# BRAWN.net
KiCad netlist of a schematic drawn in Altium Designer
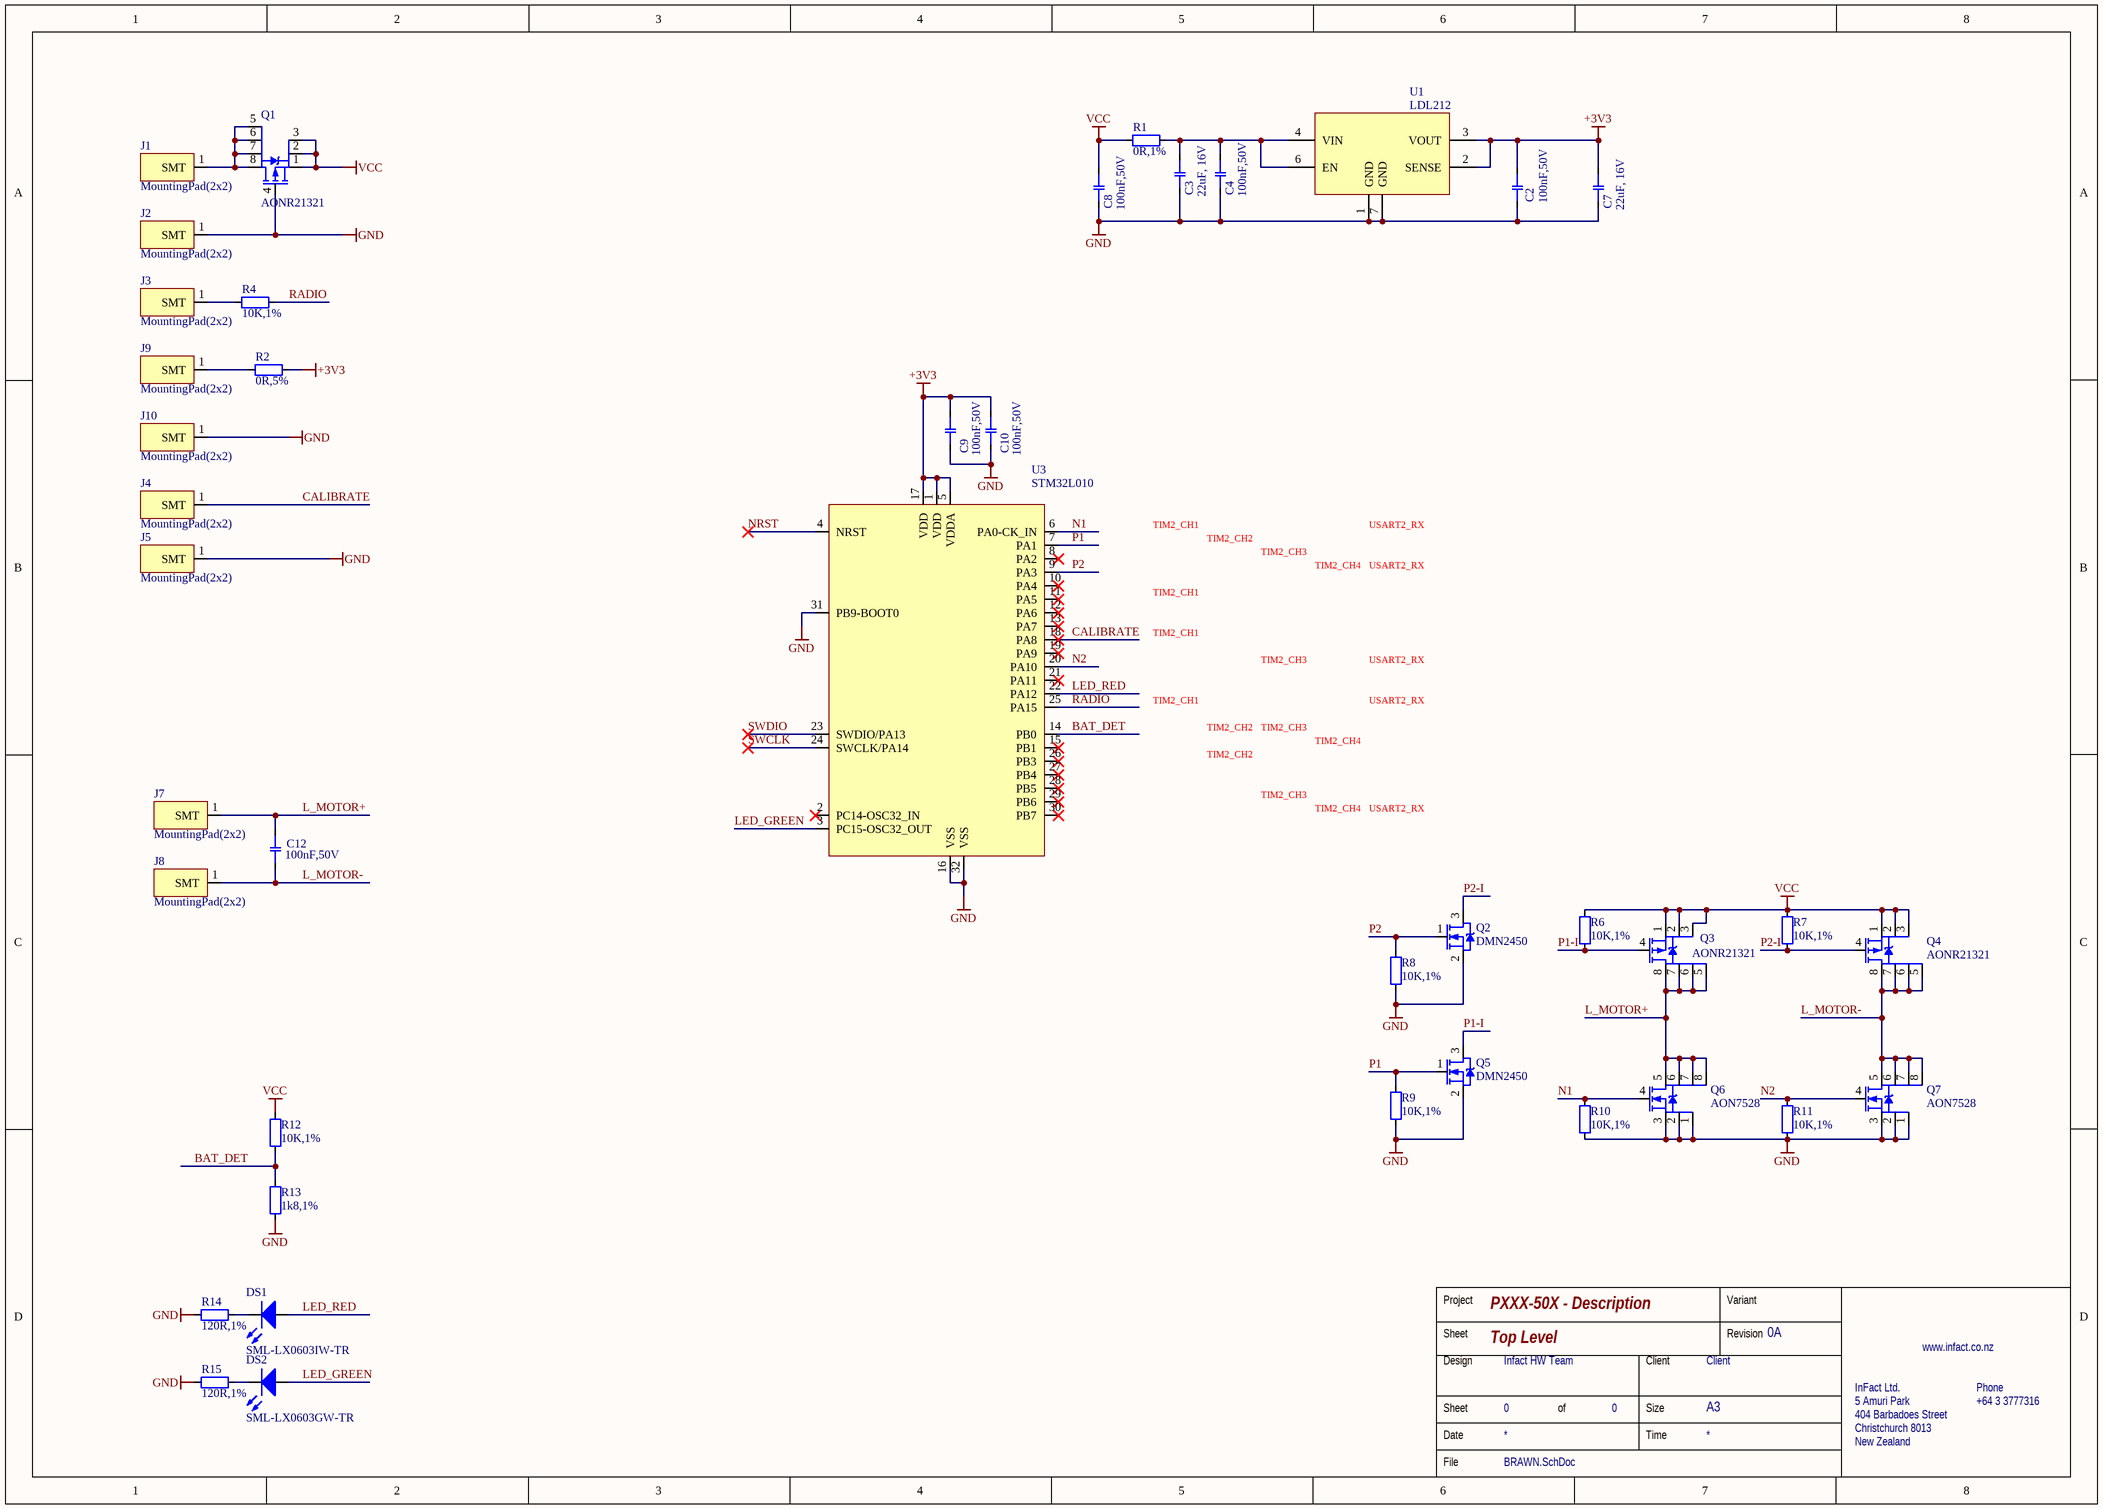
[diagram p0: BRAWN.SchDoc]

(export (version "E")
  (design (tool "Eeschema 10.0.6"))
  (components
    (comp (ref "C2")
      (value "100nF,50V")
      (footprint "CAPC1005X05N_0402")
      (description "CAP CER 100nF 50V X7R 0402")
      (fields (field (name "MANUFACTURER") "Taiyo Yuden") (field (name "TOLERANCE") "10%"))
      (libsource (lib "library") (part "CAP-NP_1"))
    )
    (comp (ref "C3")
      (value "22uF, 16V")
      (footprint "CAPC2012X12N_0805")
      (description "CAP CER 22UF 16V X5R 0805")
      (fields (field (name "MANUFACTURER") "Samsung Electro-Mechanics") (field (name "TOLERANCE") "10%"))
      (libsource (lib "library") (part "CAP-NP_1"))
    )
    (comp (ref "C4")
      (value "100nF,50V")
      (footprint "CAPC1005X05N_0402")
      (description "CAP CER 100nF 50V X7R 0402")
      (fields (field (name "MANUFACTURER") "Taiyo Yuden") (field (name "TOLERANCE") "10%"))
      (libsource (lib "library") (part "CAP-NP_1"))
    )
    (comp (ref "C7")
      (value "22uF, 16V")
      (footprint "CAPC2012X12N_0805")
      (description "CAP CER 22UF 16V X5R 0805")
      (fields (field (name "MANUFACTURER") "Samsung Electro-Mechanics") (field (name "TOLERANCE") "10%"))
      (libsource (lib "library") (part "CAP-NP_1"))
    )
    (comp (ref "C8")
      (value "100nF,50V")
      (footprint "CAPC1005X05N_0402")
      (description "CAP CER 100nF 50V X7R 0402")
      (fields (field (name "MANUFACTURER") "Taiyo Yuden") (field (name "TOLERANCE") "10%"))
      (libsource (lib "library") (part "CAP-NP_1"))
    )
    (comp (ref "C9")
      (value "100nF,50V")
      (footprint "CAPC1005X05N_0402")
      (description "CAP CER 100nF 50V X7R 0402")
      (fields (field (name "MANUFACTURER") "Taiyo Yuden") (field (name "TOLERANCE") "10%"))
      (libsource (lib "library") (part "CAP-NP_1"))
    )
    (comp (ref "C10")
      (value "100nF,50V")
      (footprint "CAPC1005X05N_0402")
      (description "CAP CER 100nF 50V X7R 0402")
      (fields (field (name "MANUFACTURER") "Taiyo Yuden") (field (name "TOLERANCE") "10%"))
      (libsource (lib "library") (part "CAP-NP_1"))
    )
    (comp (ref "C12")
      (value "100nF,50V")
      (footprint "CAPC1005X05N_0402")
      (description "CAP CER 100nF 50V X7R 0402")
      (fields (field (name "MANUFACTURER") "Taiyo Yuden") (field (name "TOLERANCE") "10%"))
      (libsource (lib "library") (part "CAP-NP_1"))
    )
    (comp (ref "DS1")
      (value "SML-LX0603IW-TR")
      (footprint "LED_SML-LX0603")
      (description "LED 635NM RED DIFF 0603 SMD")
      (fields (field (name "MANUFACTURER") "Lumex Opto/Components Inc"))
      (libsource (lib "library") (part "LED_1"))
    )
    (comp (ref "DS2")
      (value "SML-LX0603GW-TR")
      (footprint "LED_SML-LX0603")
      (description "LED 565NM GRN DIFF 0603 SMD")
      (fields (field (name "MANUFACTURER") "Lumex Opto/Components Inc"))
      (libsource (lib "library") (part "LED_1"))
    )
    (comp (ref "J1")
      (value "MountingPad(2x2)")
      (footprint "MountingPad(2x2)")
      (libsource (lib "Schlib1") (part "MountingPad(2x2)"))
    )
    (comp (ref "J2")
      (value "MountingPad(2x2)")
      (footprint "MountingPad(2x2)")
      (libsource (lib "Schlib1") (part "MountingPad(2x2)"))
    )
    (comp (ref "J3")
      (value "MountingPad(2x2)")
      (footprint "MountingPad(2x2)")
      (libsource (lib "Schlib1") (part "MountingPad(2x2)"))
    )
    (comp (ref "J4")
      (value "MountingPad(2x2)")
      (footprint "MountingPad(2x2)")
      (libsource (lib "") (part "MountingPad(2x2)_1"))
    )
    (comp (ref "J5")
      (value "MountingPad(2x2)")
      (footprint "MountingPad(2x2)")
      (libsource (lib "") (part "MountingPad(2x2)_1"))
    )
    (comp (ref "J7")
      (value "MountingPad(2x2)")
      (footprint "MountingPad(2x2)")
      (libsource (lib "") (part "MountingPad(2x2)_1"))
    )
    (comp (ref "J8")
      (value "MountingPad(2x2)")
      (footprint "MountingPad(2x2)")
      (libsource (lib "") (part "MountingPad(2x2)_1"))
    )
    (comp (ref "J9")
      (value "MountingPad(2x2)")
      (footprint "MountingPad(2x2)")
      (libsource (lib "Schlib1") (part "MountingPad(2x2)"))
    )
    (comp (ref "J10")
      (value "MountingPad(2x2)")
      (footprint "MountingPad(2x2)")
      (libsource (lib "Schlib1") (part "MountingPad(2x2)"))
    )
    (comp (ref "Q1")
      (value "AONR21321")
      (footprint "DFN3X3A_8L_EP1_P")
      (description "P-Channel 30 V 24A (Tc) 4.1W (Ta), 24W (Tc) Surface Mount 8-DFN-EP (3x3)")
      (fields (field (name "MANUFACTURER") "Alpha & Omega Semiconductor Inc."))
      (libsource (lib "library") (part "MOSFET-P_5"))
    )
    (comp (ref "Q2")
      (value "DMN2450")
      (footprint "DFN3-125x125x53")
      (description "MOSFET N-CH 20V 900MA 3DFN")
      (fields
        (field (name "MANUFACTURER") "Diodes Incorporated")
        (field (name "MANUFACTURER PART NUMBER") "DMN2450UFD-7")
      )
      (libsource (lib "library") (part "MOSFET-N_1"))
    )
    (comp (ref "Q3")
      (value "AONR21321")
      (footprint "DFN3X3A_8L_EP1_P")
      (description "P-Channel 30 V 24A (Tc) 4.1W (Ta), 24W (Tc) Surface Mount 8-DFN-EP (3x3)")
      (fields (field (name "MANUFACTURER") "Alpha & Omega Semiconductor Inc."))
      (libsource (lib "library") (part "MOSFET-P_5"))
    )
    (comp (ref "Q4")
      (value "AONR21321")
      (footprint "DFN3X3A_8L_EP1_P")
      (description "P-Channel 30 V 24A (Tc) 4.1W (Ta), 24W (Tc) Surface Mount 8-DFN-EP (3x3)")
      (fields (field (name "MANUFACTURER") "Alpha & Omega Semiconductor Inc."))
      (libsource (lib "library") (part "MOSFET-P_5"))
    )
    (comp (ref "Q5")
      (value "DMN2450")
      (footprint "DFN3-125x125x53")
      (description "MOSFET N-CH 20V 900MA 3DFN")
      (fields
        (field (name "MANUFACTURER") "Diodes Incorporated")
        (field (name "MANUFACTURER PART NUMBER") "DMN2450UFD-7")
      )
      (libsource (lib "library") (part "MOSFET-N_1"))
    )
    (comp (ref "Q6")
      (value "AON7528")
      (footprint "DFN3X3A_8L_EP1_P")
      (description "MOSFET N-CH 30V 45A/50A 8DFN")
      (fields (field (name "MANUFACTURER") "Alpha & Omega Semiconductor Inc."))
      (libsource (lib "library") (part "MOSFET-N_5"))
    )
    (comp (ref "Q7")
      (value "AON7528")
      (footprint "DFN3X3A_8L_EP1_P")
      (description "MOSFET N-CH 30V 45A/50A 8DFN")
      (fields (field (name "MANUFACTURER") "Alpha & Omega Semiconductor Inc."))
      (libsource (lib "library") (part "MOSFET-N_5"))
    )
    (comp (ref "R1")
      (value "0R,1%")
      (footprint "RESC1005X04N_0402")
      (description "RES 0R OHM 1/16W 5% 0402 SMD")
      (fields (field (name "MANUFACTURER") "Yageo") (field (name "POWER") "0.0625W"))
      (libsource (lib "") (part "RESISTOR_1_2"))
    )
    (comp (ref "R2")
      (value "0R,5%")
      (footprint "RESC1608X06N_0603")
      (description "RES 0.0 OHM 1/10W 0603 SMD")
      (fields (field (name "MANUFACTURER") "Yageo") (field (name "POWER") "0.1W"))
      (libsource (lib "") (part "RESISTOR_1_2"))
    )
    (comp (ref "R4")
      (value "10K,1%")
      (footprint "RESC1005X04N_0402")
      (description "RES 10K OHM 1/16W 1% 0402 SMD")
      (fields (field (name "MANUFACTURER") "Yageo") (field (name "POWER") "0.0625W"))
      (libsource (lib "") (part "RESISTOR_1_1"))
    )
    (comp (ref "R6")
      (value "10K,1%")
      (footprint "RESC1005X04N_0402")
      (description "RES 10K OHM 1/16W 1% 0402 SMD")
      (fields (field (name "MANUFACTURER") "Yageo") (field (name "POWER") "0.0625W"))
      (libsource (lib "library") (part "RESISTOR_1"))
    )
    (comp (ref "R7")
      (value "10K,1%")
      (footprint "RESC1005X04N_0402")
      (description "RES 10K OHM 1/16W 1% 0402 SMD")
      (fields (field (name "MANUFACTURER") "Yageo") (field (name "POWER") "0.0625W"))
      (libsource (lib "library") (part "RESISTOR_1"))
    )
    (comp (ref "R8")
      (value "10K,1%")
      (footprint "RESC1005X04N_0402")
      (description "RES 10K OHM 1/16W 1% 0402 SMD")
      (fields (field (name "MANUFACTURER") "Yageo") (field (name "POWER") "0.0625W"))
      (libsource (lib "library") (part "RESISTOR_1"))
    )
    (comp (ref "R9")
      (value "10K,1%")
      (footprint "RESC1005X04N_0402")
      (description "RES 10K OHM 1/16W 1% 0402 SMD")
      (fields (field (name "MANUFACTURER") "Yageo") (field (name "POWER") "0.0625W"))
      (libsource (lib "library") (part "RESISTOR_1"))
    )
    (comp (ref "R10")
      (value "10K,1%")
      (footprint "RESC1005X04N_0402")
      (description "RES 10K OHM 1/16W 1% 0402 SMD")
      (fields (field (name "MANUFACTURER") "Yageo") (field (name "POWER") "0.0625W"))
      (libsource (lib "library") (part "RESISTOR_1"))
    )
    (comp (ref "R11")
      (value "10K,1%")
      (footprint "RESC1005X04N_0402")
      (description "RES 10K OHM 1/16W 1% 0402 SMD")
      (fields (field (name "MANUFACTURER") "Yageo") (field (name "POWER") "0.0625W"))
      (libsource (lib "library") (part "RESISTOR_1"))
    )
    (comp (ref "R12")
      (value "10K,1%")
      (footprint "RESC1005X04N_0402")
      (description "RES 10K OHM 1/16W 1% 0402 SMD")
      (fields (field (name "MANUFACTURER") "Yageo") (field (name "POWER") "0.0625W"))
      (libsource (lib "library") (part "RESISTOR_1"))
    )
    (comp (ref "R13")
      (value "1k8,1%")
      (footprint "RESC1005X04N_0402")
      (description "RES 1k8 0.0625W 1% 0402 SMD")
      (fields (field (name "MANUFACTURER") "Vishay Dale") (field (name "POWER") "0.0625W"))
      (libsource (lib "library") (part "RESISTOR_1"))
    )
    (comp (ref "R14")
      (value "120R,1%")
      (footprint "RESC1005X04N_0402")
      (description "RES 120 OHM 1/16W 0402 SMD")
      (fields (field (name "MANUFACTURER") "Yageo") (field (name "POWER") "0.0625W"))
      (libsource (lib "") (part "RESISTOR_1_1"))
    )
    (comp (ref "R15")
      (value "120R,1%")
      (footprint "RESC1005X04N_0402")
      (description "RES 120 OHM 1/16W 0402 SMD")
      (fields (field (name "MANUFACTURER") "Yageo") (field (name "POWER") "0.0625W"))
      (libsource (lib "") (part "RESISTOR_1_1"))
    )
    (comp (ref "U1")
      (value "LDL212")
      (footprint "DFN50P200X200X80-8N_PWSON6")
      (description "1.2A 3V3 LDO LINEAR REGULATOR")
      (fields
        (field (name "MANUFACTURER") "STMicroelectronics")
        (field (name "MANUFACTURER PART NUMBER") "LDL212PV33R")
      )
      (libsource (lib "library") (part "LDL212PU50R"))
    )
    (comp (ref "U3")
      (value "STM32L010")
      (footprint "TSQFP50P700X700X160-32N")
      (description "ARM® Cortex®-M0+ series Microcontroller IC 32-Bit 32MHz 16KB (16K x 8) FLASH 32-LQFP (7x7)")
      (fields
        (field (name "MANUFACTURER") "STMicroelectronics")
        (field (name "MANUFACTURER PART NUMBER") "STM32L010K4T6")
      )
      (libsource (lib "library") (part "STM32L010F4/K4"))
    )
  )
  (nets
    (net (code "1") (name "+3V3") (class "Default")
      (node (ref "C10") (pin "2") (pinfunction "2_2") (pintype "passive"))
      (node (ref "C2") (pin "2") (pinfunction "2_2") (pintype "passive"))
      (node (ref "C7") (pin "2") (pinfunction "2_2") (pintype "passive"))
      (node (ref "C9") (pin "2") (pinfunction "2_2") (pintype "passive"))
      (node (ref "R2") (pin "2") (pinfunction "2_2") (pintype "passive"))
      (node (ref "U1") (pin "2") (pinfunction "SENSE_2") (pintype "passive"))
      (node (ref "U1") (pin "3") (pinfunction "VOUT_3") (pintype "passive"))
      (node (ref "U3") (pin "1") (pinfunction "VDD_1") (pintype "passive"))
      (node (ref "U3") (pin "17") (pinfunction "VDD_17") (pintype "passive"))
      (node (ref "U3") (pin "5") (pinfunction "VDDA_5") (pintype "passive"))
    )
    (net (code "2") (name "/BAT_DET") (class "Default")
      (node (ref "R12") (pin "2") (pinfunction "2_2") (pintype "passive"))
      (node (ref "R13") (pin "1") (pinfunction "1_1") (pintype "passive"))
      (node (ref "U3") (pin "14") (pinfunction "PB0_14") (pintype "passive"))
    )
    (net (code "3") (name "/CALIBRATE") (class "Default")
      (node (ref "J4") (pin "1") (pinfunction "SMT_1") (pintype "passive"))
      (node (ref "U3") (pin "18") (pinfunction "PA8_18") (pintype "passive"))
    )
    (net (code "4") (name "/LED_GREEN") (class "Default")
      (node (ref "DS2") (pin "2") (pinfunction "A_2") (pintype "passive"))
      (node (ref "U3") (pin "3") (pinfunction "PC15-OSC32_OUT_3") (pintype "passive"))
    )
    (net (code "5") (name "/LED_RED") (class "Default")
      (node (ref "DS1") (pin "2") (pinfunction "A_2") (pintype "passive"))
      (node (ref "U3") (pin "22") (pinfunction "PA12_22") (pintype "passive"))
    )
    (net (code "6") (name "/L_MOTOR+") (class "Default")
      (node (ref "C12") (pin "2") (pinfunction "2_2") (pintype "passive"))
      (node (ref "J7") (pin "1") (pinfunction "SMT_1") (pintype "passive"))
      (node (ref "Q3") (pin "5") (pinfunction "D_5") (pintype "passive"))
      (node (ref "Q3") (pin "6") (pinfunction "D_6") (pintype "passive"))
      (node (ref "Q3") (pin "7") (pinfunction "D_7") (pintype "passive"))
      (node (ref "Q3") (pin "8") (pinfunction "D_8") (pintype "passive"))
      (node (ref "Q6") (pin "5") (pinfunction "D_5") (pintype "passive"))
      (node (ref "Q6") (pin "6") (pinfunction "D_6") (pintype "passive"))
      (node (ref "Q6") (pin "7") (pinfunction "D_7") (pintype "passive"))
      (node (ref "Q6") (pin "8") (pinfunction "D_8") (pintype "passive"))
    )
    (net (code "7") (name "/L_MOTOR-") (class "Default")
      (node (ref "C12") (pin "1") (pinfunction "1_1") (pintype "passive"))
      (node (ref "J8") (pin "1") (pinfunction "SMT_1") (pintype "passive"))
      (node (ref "Q4") (pin "5") (pinfunction "D_5") (pintype "passive"))
      (node (ref "Q4") (pin "6") (pinfunction "D_6") (pintype "passive"))
      (node (ref "Q4") (pin "7") (pinfunction "D_7") (pintype "passive"))
      (node (ref "Q4") (pin "8") (pinfunction "D_8") (pintype "passive"))
      (node (ref "Q7") (pin "5") (pinfunction "D_5") (pintype "passive"))
      (node (ref "Q7") (pin "6") (pinfunction "D_6") (pintype "passive"))
      (node (ref "Q7") (pin "7") (pinfunction "D_7") (pintype "passive"))
      (node (ref "Q7") (pin "8") (pinfunction "D_8") (pintype "passive"))
    )
    (net (code "8") (name "/N1") (class "Default")
      (node (ref "Q6") (pin "4") (pinfunction "G_4") (pintype "passive"))
      (node (ref "R10") (pin "1") (pinfunction "1_1") (pintype "passive"))
      (node (ref "U3") (pin "6") (pinfunction "PA0-CK_IN_6") (pintype "passive"))
    )
    (net (code "9") (name "/N2") (class "Default")
      (node (ref "Q7") (pin "4") (pinfunction "G_4") (pintype "passive"))
      (node (ref "R11") (pin "1") (pinfunction "1_1") (pintype "passive"))
      (node (ref "U3") (pin "20") (pinfunction "PA10_20") (pintype "passive"))
    )
    (net (code "10") (name "/NRST") (class "Default")
      (node (ref "U3") (pin "4") (pinfunction "NRST_4") (pintype "passive+no_connect"))
    )
    (net (code "11") (name "/P1") (class "Default")
      (node (ref "Q5") (pin "1") (pinfunction "G_1") (pintype "passive"))
      (node (ref "R9") (pin "1") (pinfunction "1_1") (pintype "passive"))
      (node (ref "U3") (pin "7") (pinfunction "PA1_7") (pintype "passive"))
    )
    (net (code "12") (name "/P1-I") (class "Default")
      (node (ref "Q3") (pin "4") (pinfunction "G_4") (pintype "passive"))
      (node (ref "Q5") (pin "3") (pinfunction "D_3") (pintype "passive"))
      (node (ref "R6") (pin "2") (pinfunction "2_2") (pintype "passive"))
    )
    (net (code "13") (name "/P2") (class "Default")
      (node (ref "Q2") (pin "1") (pinfunction "G_1") (pintype "passive"))
      (node (ref "R8") (pin "1") (pinfunction "1_1") (pintype "passive"))
      (node (ref "U3") (pin "9") (pinfunction "PA3_9") (pintype "passive"))
    )
    (net (code "14") (name "/P2-I") (class "Default")
      (node (ref "Q2") (pin "3") (pinfunction "D_3") (pintype "passive"))
      (node (ref "Q4") (pin "4") (pinfunction "G_4") (pintype "passive"))
      (node (ref "R7") (pin "2") (pinfunction "2_2") (pintype "passive"))
    )
    (net (code "15") (name "/RADIO") (class "Default")
      (node (ref "R4") (pin "2") (pinfunction "2_2") (pintype "passive"))
      (node (ref "U3") (pin "25") (pinfunction "PA15_25") (pintype "passive"))
    )
    (net (code "16") (name "/SWCLK") (class "Default")
      (node (ref "U3") (pin "24") (pinfunction "SWCLK/PA14_24") (pintype "passive+no_connect"))
    )
    (net (code "17") (name "/SWDIO") (class "Default")
      (node (ref "U3") (pin "23") (pinfunction "SWDIO/PA13_23") (pintype "passive+no_connect"))
    )
    (net (code "18") (name "GND") (class "Default")
      (node (ref "C10") (pin "1") (pinfunction "1_1") (pintype "passive"))
      (node (ref "C2") (pin "1") (pinfunction "1_1") (pintype "passive"))
      (node (ref "C3") (pin "1") (pinfunction "1_1") (pintype "passive"))
      (node (ref "C4") (pin "1") (pinfunction "1_1") (pintype "passive"))
      (node (ref "C7") (pin "1") (pinfunction "1_1") (pintype "passive"))
      (node (ref "C8") (pin "1") (pinfunction "1_1") (pintype "passive"))
      (node (ref "C9") (pin "1") (pinfunction "1_1") (pintype "passive"))
      (node (ref "J10") (pin "1") (pinfunction "SMT_1") (pintype "passive"))
      (node (ref "J2") (pin "1") (pinfunction "SMT_1") (pintype "passive"))
      (node (ref "J5") (pin "1") (pinfunction "SMT_1") (pintype "passive"))
      (node (ref "Q1") (pin "4") (pinfunction "G_4") (pintype "passive"))
      (node (ref "Q2") (pin "2") (pinfunction "S_2") (pintype "passive"))
      (node (ref "Q5") (pin "2") (pinfunction "S_2") (pintype "passive"))
      (node (ref "Q6") (pin "1") (pinfunction "S_1") (pintype "passive"))
      (node (ref "Q6") (pin "2") (pinfunction "S_2") (pintype "passive"))
      (node (ref "Q6") (pin "3") (pinfunction "S_3") (pintype "passive"))
      (node (ref "Q7") (pin "1") (pinfunction "S_1") (pintype "passive"))
      (node (ref "Q7") (pin "2") (pinfunction "S_2") (pintype "passive"))
      (node (ref "Q7") (pin "3") (pinfunction "S_3") (pintype "passive"))
      (node (ref "R10") (pin "2") (pinfunction "2_2") (pintype "passive"))
      (node (ref "R11") (pin "2") (pinfunction "2_2") (pintype "passive"))
      (node (ref "R13") (pin "2") (pinfunction "2_2") (pintype "passive"))
      (node (ref "R14") (pin "1") (pinfunction "1_1") (pintype "passive"))
      (node (ref "R15") (pin "1") (pinfunction "1_1") (pintype "passive"))
      (node (ref "R8") (pin "2") (pinfunction "2_2") (pintype "passive"))
      (node (ref "R9") (pin "2") (pinfunction "2_2") (pintype "passive"))
      (node (ref "U1") (pin "1") (pinfunction "GND_1") (pintype "passive"))
      (node (ref "U1") (pin "7") (pinfunction "GND_7") (pintype "passive"))
      (node (ref "U3") (pin "16") (pinfunction "VSS_16") (pintype "passive"))
      (node (ref "U3") (pin "31") (pinfunction "PB9-BOOT0_31") (pintype "passive"))
      (node (ref "U3") (pin "32") (pinfunction "VSS_32") (pintype "passive"))
    )
    (net (code "19") (name "Net-(DS1-C)") (class "Default")
      (node (ref "DS1") (pin "1") (pinfunction "C_1") (pintype "passive"))
      (node (ref "R14") (pin "2") (pinfunction "2_2") (pintype "passive"))
    )
    (net (code "20") (name "Net-(DS2-C)") (class "Default")
      (node (ref "DS2") (pin "1") (pinfunction "C_1") (pintype "passive"))
      (node (ref "R15") (pin "2") (pinfunction "2_2") (pintype "passive"))
    )
    (net (code "21") (name "Net-(J1-SMT)") (class "Default")
      (node (ref "J1") (pin "1") (pinfunction "SMT_1") (pintype "passive"))
      (node (ref "Q1") (pin "5") (pinfunction "D_5") (pintype "passive"))
      (node (ref "Q1") (pin "6") (pinfunction "D_6") (pintype "passive"))
      (node (ref "Q1") (pin "7") (pinfunction "D_7") (pintype "passive"))
      (node (ref "Q1") (pin "8") (pinfunction "D_8") (pintype "passive"))
    )
    (net (code "22") (name "Net-(J3-SMT)") (class "Default")
      (node (ref "J3") (pin "1") (pinfunction "SMT_1") (pintype "passive"))
      (node (ref "R4") (pin "1") (pinfunction "1_1") (pintype "passive"))
    )
    (net (code "23") (name "Net-(J9-SMT)") (class "Default")
      (node (ref "J9") (pin "1") (pinfunction "SMT_1") (pintype "passive"))
      (node (ref "R2") (pin "1") (pinfunction "1_1") (pintype "passive"))
    )
    (net (code "24") (name "Net-(U1-EN)") (class "Default")
      (node (ref "C3") (pin "2") (pinfunction "2_2") (pintype "passive"))
      (node (ref "C4") (pin "2") (pinfunction "2_2") (pintype "passive"))
      (node (ref "R1") (pin "2") (pinfunction "2_2") (pintype "passive"))
      (node (ref "U1") (pin "4") (pinfunction "VIN_4") (pintype "passive"))
      (node (ref "U1") (pin "6") (pinfunction "EN_6") (pintype "passive"))
    )
    (net (code "25") (name "VCC") (class "Default")
      (node (ref "C8") (pin "2") (pinfunction "2_2") (pintype "passive"))
      (node (ref "Q1") (pin "1") (pinfunction "S_1") (pintype "passive"))
      (node (ref "Q1") (pin "2") (pinfunction "S_2") (pintype "passive"))
      (node (ref "Q1") (pin "3") (pinfunction "S_3") (pintype "passive"))
      (node (ref "Q3") (pin "1") (pinfunction "S_1") (pintype "passive"))
      (node (ref "Q3") (pin "2") (pinfunction "S_2") (pintype "passive"))
      (node (ref "Q3") (pin "3") (pinfunction "S_3") (pintype "passive"))
      (node (ref "Q4") (pin "1") (pinfunction "S_1") (pintype "passive"))
      (node (ref "Q4") (pin "2") (pinfunction "S_2") (pintype "passive"))
      (node (ref "Q4") (pin "3") (pinfunction "S_3") (pintype "passive"))
      (node (ref "R1") (pin "1") (pinfunction "1_1") (pintype "passive"))
      (node (ref "R12") (pin "1") (pinfunction "1_1") (pintype "passive"))
      (node (ref "R6") (pin "1") (pinfunction "1_1") (pintype "passive"))
      (node (ref "R7") (pin "1") (pinfunction "1_1") (pintype "passive"))
    )
    (net (code "26") (name "unconnected-(U3-PA2-Pad8)") (class "Default")
      (node (ref "U3") (pin "8") (pinfunction "PA2_8") (pintype "passive+no_connect"))
    )
    (net (code "27") (name "unconnected-(U3-PA4-Pad10)") (class "Default")
      (node (ref "U3") (pin "10") (pinfunction "PA4_10") (pintype "passive+no_connect"))
    )
    (net (code "28") (name "unconnected-(U3-PA5-Pad11)") (class "Default")
      (node (ref "U3") (pin "11") (pinfunction "PA5_11") (pintype "passive+no_connect"))
    )
    (net (code "29") (name "unconnected-(U3-PA6-Pad12)") (class "Default")
      (node (ref "U3") (pin "12") (pinfunction "PA6_12") (pintype "passive+no_connect"))
    )
    (net (code "30") (name "unconnected-(U3-PA7-Pad13)") (class "Default")
      (node (ref "U3") (pin "13") (pinfunction "PA7_13") (pintype "passive+no_connect"))
    )
    (net (code "31") (name "unconnected-(U3-PA9-Pad19)") (class "Default")
      (node (ref "U3") (pin "19") (pinfunction "PA9_19") (pintype "passive+no_connect"))
    )
    (net (code "32") (name "unconnected-(U3-PA11-Pad21)") (class "Default")
      (node (ref "U3") (pin "21") (pinfunction "PA11_21") (pintype "passive+no_connect"))
    )
    (net (code "33") (name "unconnected-(U3-PB1-Pad15)") (class "Default")
      (node (ref "U3") (pin "15") (pinfunction "PB1_15") (pintype "passive+no_connect"))
    )
    (net (code "34") (name "unconnected-(U3-PB3-Pad26)") (class "Default")
      (node (ref "U3") (pin "26") (pinfunction "PB3_26") (pintype "passive+no_connect"))
    )
    (net (code "35") (name "unconnected-(U3-PB4-Pad27)") (class "Default")
      (node (ref "U3") (pin "27") (pinfunction "PB4_27") (pintype "passive+no_connect"))
    )
    (net (code "36") (name "unconnected-(U3-PB5-Pad28)") (class "Default")
      (node (ref "U3") (pin "28") (pinfunction "PB5_28") (pintype "passive+no_connect"))
    )
    (net (code "37") (name "unconnected-(U3-PB6-Pad29)") (class "Default")
      (node (ref "U3") (pin "29") (pinfunction "PB6_29") (pintype "passive+no_connect"))
    )
    (net (code "38") (name "unconnected-(U3-PB7-Pad30)") (class "Default")
      (node (ref "U3") (pin "30") (pinfunction "PB7_30") (pintype "passive+no_connect"))
    )
    (net (code "39") (name "unconnected-(U3-PC14-OSC32_IN-Pad2)") (class "Default")
      (node (ref "U3") (pin "2") (pinfunction "PC14-OSC32_IN_2") (pintype "passive+no_connect"))
    )
  )
)
